# RTC.net
KiCad netlist of a schematic drawn in Altium Designer
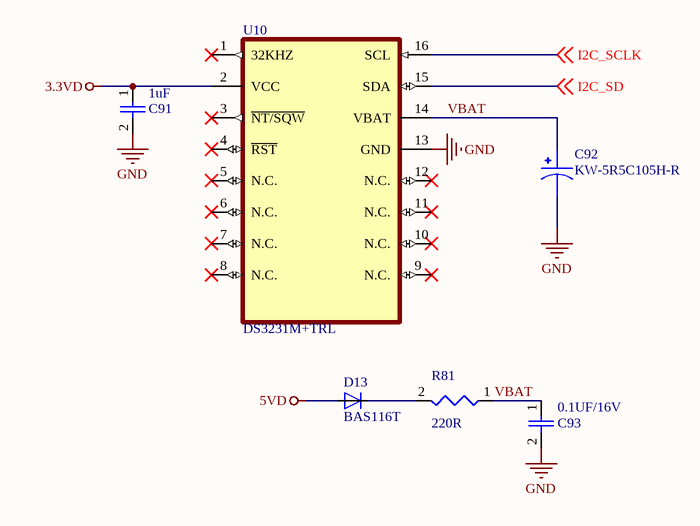
[diagram p0: RTC.SchDoc]

(export (version "E")
  (design (tool "Eeschema 10.0.6"))
  (components
    (comp (ref "C91") (value "1uF") (footprint "0603-C") (libsource (lib "OOLITEV8") (part "CAP")))
    (comp (ref "C92")
      (value "KW-5R5C105H-R")
      (footprint "CAPPRD500W80D2150H950")
      (description "Supercapacitors 1F 5.5V")
      (fields (field (name "MP") "DK-6R3D105T") (field (name "MF") "Elna"))
      (libsource (lib "OOLITEV8") (part "DK-6R3D105T"))
    )
    (comp (ref "C93") (value "0.1UF/16V") (footprint "0603-C") (libsource (lib "OOLITEV8") (part "CAP")))
    (comp (ref "D13")
      (value "BAS116T")
      (footprint "SOT416")
      (description "Diode Standard 75V 200mA Surface Mount SC-75, SOT-416")
      (fields (field (name "MP") "BAS116") (field (name "MF") "NXP Semiconductors"))
      (libsource (lib "OOLITEV8") (part "BAS116T"))
    )
    (comp (ref "R81") (value "220R") (footprint "0603-R") (libsource (lib "OOLITEV8") (part "Res")))
    (comp (ref "U10")
      (value "DS3231M+TRL")
      (footprint "SOIC127P1032X265-16N")
      (libsource (lib "OOLITEV8") (part "DS3231M+TRL"))
    )
  )
  (nets
    (net (code "1") (name "/VBAT") (class "Default")
      (node (ref "C92") (pin "1") (pinfunction "1_1") (pintype "passive"))
      (node (ref "C93") (pin "1") (pinfunction "1_1") (pintype "passive"))
      (node (ref "R81") (pin "1") (pinfunction "1_1") (pintype "passive"))
      (node (ref "U10") (pin "14") (pinfunction "VBAT_14") (pintype "power_in"))
    )
    (net (code "2") (name "3.3VD") (class "Default")
      (node (ref "C91") (pin "1") (pinfunction "1_1") (pintype "passive"))
      (node (ref "U10") (pin "2") (pinfunction "VCC_2") (pintype "power_in"))
    )
    (net (code "3") (name "5VD") (class "Default")
      (node (ref "D13") (pin "1") (pinfunction "A_1") (pintype "passive"))
    )
    (net (code "4") (name "GND") (class "Default")
      (node (ref "C91") (pin "2") (pinfunction "2_2") (pintype "passive"))
      (node (ref "C92") (pin "2") (pinfunction "2_2") (pintype "passive"))
      (node (ref "C93") (pin "2") (pinfunction "2_2") (pintype "passive"))
      (node (ref "U10") (pin "13") (pinfunction "GND_13") (pintype "power_in"))
    )
    (net (code "5") (name "I2C_SCLK") (class "Default")
      (node (ref "U10") (pin "16") (pinfunction "SCL_16") (pintype "input"))
    )
    (net (code "6") (name "I2C_SD") (class "Default")
      (node (ref "U10") (pin "15") (pinfunction "SDA_15") (pintype "bidirectional"))
    )
    (net (code "7") (name "Net-(D13-K)") (class "Default")
      (node (ref "D13") (pin "3") (pinfunction "K_3") (pintype "passive"))
      (node (ref "R81") (pin "2") (pinfunction "2_2") (pintype "passive"))
    )
    (net (code "8") (name "unconnected-(U10-32KHZ-Pad1)") (class "Default")
      (node (ref "U10") (pin "1") (pinfunction "32KHZ_1") (pintype "output+no_connect"))
    )
    (net (code "9") (name "unconnected-(U10-N.C.-Pad5)") (class "Default")
      (node (ref "U10") (pin "5") (pinfunction "N.C._5") (pintype "bidirectional+no_connect"))
    )
    (net (code "10") (name "unconnected-(U10-N.C.-Pad6)") (class "Default")
      (node (ref "U10") (pin "6") (pinfunction "N.C._6") (pintype "bidirectional+no_connect"))
    )
    (net (code "11") (name "unconnected-(U10-N.C.-Pad7)") (class "Default")
      (node (ref "U10") (pin "7") (pinfunction "N.C._7") (pintype "bidirectional+no_connect"))
    )
    (net (code "12") (name "unconnected-(U10-N.C.-Pad8)") (class "Default")
      (node (ref "U10") (pin "8") (pinfunction "N.C._8") (pintype "bidirectional+no_connect"))
    )
    (net (code "13") (name "unconnected-(U10-N.C.-Pad9)") (class "Default")
      (node (ref "U10") (pin "9") (pinfunction "N.C._9") (pintype "bidirectional+no_connect"))
    )
    (net (code "14") (name "unconnected-(U10-N.C.-Pad10)") (class "Default")
      (node (ref "U10") (pin "10") (pinfunction "N.C._10") (pintype "bidirectional+no_connect"))
    )
    (net (code "15") (name "unconnected-(U10-N.C.-Pad11)") (class "Default")
      (node (ref "U10") (pin "11") (pinfunction "N.C._11") (pintype "bidirectional+no_connect"))
    )
    (net (code "16") (name "unconnected-(U10-N.C.-Pad12)") (class "Default")
      (node (ref "U10") (pin "12") (pinfunction "N.C._12") (pintype "bidirectional+no_connect"))
    )
    (net (code "17") (name "unconnected-(U10-~{NT{slash}SQW}-Pad3)") (class "Default")
      (node (ref "U10") (pin "3") (pinfunction "~{NT/SQW}_3") (pintype "output+no_connect"))
    )
    (net (code "18") (name "unconnected-(U10-~{RST}-Pad4)") (class "Default")
      (node (ref "U10") (pin "4") (pinfunction "~{RST}_4") (pintype "bidirectional+no_connect"))
    )
  )
)
